# Tag_Reader_r1.net
KiCad netlist of a schematic drawn in EAGLE
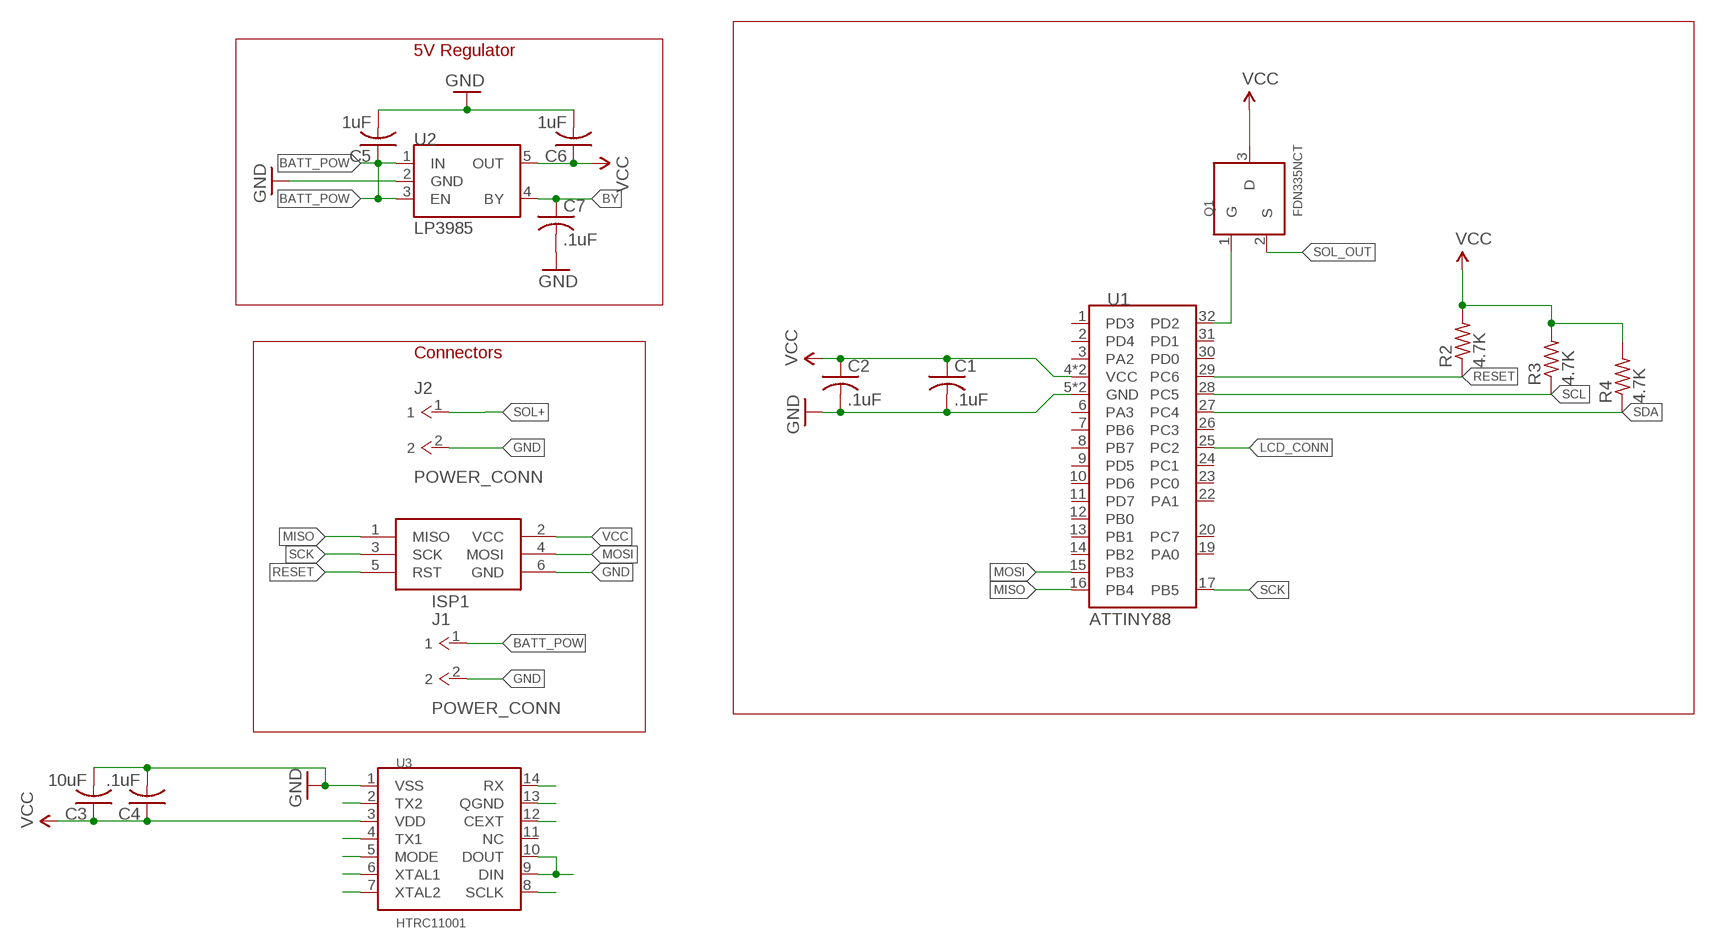
[diagram p0: schematic, sheet 1]

(export (version "E")
  (design (tool "Eeschema 10.0.6"))
  (components
    (comp (ref "C1")
      (value ".1uF")
      (footprint "eagle-import:C0603")
      (libsource (lib "eagle-import") (part "C-USC0603"))
    )
    (comp (ref "C2")
      (value ".1uF")
      (footprint "eagle-import:C0603")
      (libsource (lib "eagle-import") (part "C-USC0603"))
    )
    (comp (ref "C3")
      (value "10uF")
      (footprint "eagle-import:C0603")
      (libsource (lib "eagle-import") (part "C-USC0603"))
    )
    (comp (ref "C4")
      (value ".1uF")
      (footprint "eagle-import:C0603")
      (libsource (lib "eagle-import") (part "C-USC0603"))
    )
    (comp (ref "C5")
      (value "1uF")
      (footprint "eagle-import:C0603")
      (libsource (lib "eagle-import") (part "C-USC0603"))
    )
    (comp (ref "C6")
      (value "1uF")
      (footprint "eagle-import:C0603")
      (libsource (lib "eagle-import") (part "C-USC0603"))
    )
    (comp (ref "C7")
      (value ".1uF")
      (footprint "eagle-import:C0603")
      (libsource (lib "eagle-import") (part "C-USC0603"))
    )
    (comp (ref "ISP1")
      (value "AVRISP-6")
      (footprint "eagle-import:AVRISP")
      (libsource (lib "eagle-import") (part "AVRISP-6"))
    )
    (comp (ref "J1")
      (value "POWER_CONN")
      (footprint "eagle-import:640455_CONN")
      (libsource (lib "eagle-import") (part "POWER_CONN"))
    )
    (comp (ref "J2")
      (value "POWER_CONN")
      (footprint "eagle-import:640455_CONN")
      (libsource (lib "eagle-import") (part "POWER_CONN"))
    )
    (comp (ref "Q1")
      (value "FDN335NCT")
      (footprint "eagle-import:SOT23-3")
      (libsource (lib "eagle-import") (part "FDN335NCT"))
    )
    (comp (ref "R2")
      (value "4.7K")
      (footprint "eagle-import:R0603")
      (libsource (lib "eagle-import") (part "R-US_R0603"))
    )
    (comp (ref "R3")
      (value "4.7K")
      (footprint "eagle-import:R0603")
      (libsource (lib "eagle-import") (part "R-US_R0603"))
    )
    (comp (ref "R4")
      (value "4.7K")
      (footprint "eagle-import:R0603")
      (libsource (lib "eagle-import") (part "R-US_R0603"))
    )
    (comp (ref "U1")
      (value "ATTINY88")
      (footprint "eagle-import:32-TQFP")
      (libsource (lib "eagle-import") (part "ATTINY88"))
    )
    (comp (ref "U2")
      (value "LP3985")
      (footprint "eagle-import:SOT23-5")
      (libsource (lib "eagle-import") (part "LP3985"))
    )
    (comp (ref "U3")
      (value "HTRC11001")
      (footprint "eagle-import:14-SOIC")
      (libsource (lib "eagle-import") (part "HTRC11001"))
    )
  )
  (nets
    (net (code "1") (name "BATT_POW") (class "Default")
      (node (ref "C5") (pin "1") (pinfunction "1_1") (pintype "passive"))
      (node (ref "J1") (pin "1") (pinfunction "1_1") (pintype "bidirectional"))
      (node (ref "U2") (pin "1") (pinfunction "IN_1") (pintype "bidirectional"))
      (node (ref "U2") (pin "3") (pinfunction "EN_3") (pintype "bidirectional"))
    )
    (net (code "2") (name "BY") (class "Default")
      (node (ref "C7") (pin "1") (pinfunction "1_1") (pintype "passive"))
      (node (ref "U2") (pin "4") (pinfunction "BY_4") (pintype "bidirectional"))
    )
    (net (code "3") (name "GND") (class "Default")
      (node (ref "C1") (pin "2") (pinfunction "2_2") (pintype "passive"))
      (node (ref "C2") (pin "2") (pinfunction "2_2") (pintype "passive"))
      (node (ref "C3") (pin "2") (pinfunction "2_2") (pintype "passive"))
      (node (ref "C4") (pin "2") (pinfunction "2_2") (pintype "passive"))
      (node (ref "C5") (pin "2") (pinfunction "2_2") (pintype "passive"))
      (node (ref "C6") (pin "2") (pinfunction "2_2") (pintype "passive"))
      (node (ref "C7") (pin "2") (pinfunction "2_2") (pintype "passive"))
      (node (ref "ISP1") (pin "6") (pinfunction "GND_6") (pintype "power_in"))
      (node (ref "J1") (pin "2") (pinfunction "2_2") (pintype "bidirectional"))
      (node (ref "J2") (pin "2") (pinfunction "2_2") (pintype "bidirectional"))
      (node (ref "U1") (pin "21") (pinfunction "GND_21") (pintype "bidirectional"))
      (node (ref "U1") (pin "5") (pinfunction "GND_5") (pintype "bidirectional"))
      (node (ref "U2") (pin "2") (pinfunction "GND_2") (pintype "bidirectional"))
      (node (ref "U3") (pin "1") (pinfunction "VSS_1") (pintype "bidirectional"))
    )
    (net (code "4") (name "LCD_CONN") (class "Default")
      (node (ref "U1") (pin "25") (pinfunction "PC2_25") (pintype "bidirectional"))
    )
    (net (code "5") (name "MISO") (class "Default")
      (node (ref "ISP1") (pin "1") (pinfunction "MISO_1") (pintype "input"))
      (node (ref "U1") (pin "16") (pinfunction "PB4_16") (pintype "bidirectional"))
    )
    (net (code "6") (name "MOSI") (class "Default")
      (node (ref "ISP1") (pin "4") (pinfunction "MOSI_4") (pintype "output"))
      (node (ref "U1") (pin "15") (pinfunction "PB3_15") (pintype "bidirectional"))
    )
    (net (code "7") (name "Net-(Q1-G)") (class "Default")
      (node (ref "Q1") (pin "1") (pinfunction "G_1") (pintype "bidirectional"))
      (node (ref "U1") (pin "32") (pinfunction "PD2_32") (pintype "bidirectional"))
    )
    (net (code "8") (name "Net-(U3-DIN)") (class "Default")
      (node (ref "U3") (pin "10") (pinfunction "DOUT_10") (pintype "bidirectional"))
      (node (ref "U3") (pin "9") (pinfunction "DIN_9") (pintype "bidirectional"))
    )
    (net (code "9") (name "RESET") (class "Default")
      (node (ref "ISP1") (pin "5") (pinfunction "RST_5") (pintype "output"))
      (node (ref "R2") (pin "1") (pinfunction "1_1") (pintype "passive"))
      (node (ref "U1") (pin "29") (pinfunction "PC6_29") (pintype "bidirectional"))
    )
    (net (code "10") (name "SCK") (class "Default")
      (node (ref "ISP1") (pin "3") (pinfunction "SCK_3") (pintype "output"))
      (node (ref "U1") (pin "17") (pinfunction "PB5_17") (pintype "bidirectional"))
    )
    (net (code "11") (name "SCL") (class "Default")
      (node (ref "R3") (pin "1") (pinfunction "1_1") (pintype "passive"))
      (node (ref "U1") (pin "28") (pinfunction "PC5_28") (pintype "bidirectional"))
    )
    (net (code "12") (name "SDA") (class "Default")
      (node (ref "R4") (pin "1") (pinfunction "1_1") (pintype "passive"))
      (node (ref "U1") (pin "27") (pinfunction "PC4_27") (pintype "bidirectional"))
    )
    (net (code "13") (name "SOL+") (class "Default")
      (node (ref "J2") (pin "1") (pinfunction "1_1") (pintype "bidirectional"))
    )
    (net (code "14") (name "SOL_OUT") (class "Default")
      (node (ref "Q1") (pin "2") (pinfunction "S_2") (pintype "bidirectional"))
    )
    (net (code "15") (name "VCC") (class "Default")
      (node (ref "C1") (pin "1") (pinfunction "1_1") (pintype "passive"))
      (node (ref "C2") (pin "1") (pinfunction "1_1") (pintype "passive"))
      (node (ref "C3") (pin "1") (pinfunction "1_1") (pintype "passive"))
      (node (ref "C4") (pin "1") (pinfunction "1_1") (pintype "passive"))
      (node (ref "C6") (pin "1") (pinfunction "1_1") (pintype "passive"))
      (node (ref "ISP1") (pin "2") (pinfunction "VCC_2") (pintype "power_in"))
      (node (ref "Q1") (pin "3") (pinfunction "D_3") (pintype "bidirectional"))
      (node (ref "R2") (pin "2") (pinfunction "2_2") (pintype "passive"))
      (node (ref "R3") (pin "2") (pinfunction "2_2") (pintype "passive"))
      (node (ref "R4") (pin "2") (pinfunction "2_2") (pintype "passive"))
      (node (ref "U1") (pin "18") (pinfunction "VCC_18") (pintype "bidirectional"))
      (node (ref "U1") (pin "4") (pinfunction "VCC_4") (pintype "bidirectional"))
      (node (ref "U2") (pin "5") (pinfunction "OUT_5") (pintype "bidirectional"))
      (node (ref "U3") (pin "3") (pinfunction "VDD_3") (pintype "bidirectional"))
    )
    (net (code "16") (name "unconnected-(U1-PA0-Pad19)") (class "Default")
      (node (ref "U1") (pin "19") (pinfunction "PA0_19") (pintype "bidirectional"))
    )
    (net (code "17") (name "unconnected-(U1-PA1-Pad22)") (class "Default")
      (node (ref "U1") (pin "22") (pinfunction "PA1_22") (pintype "bidirectional"))
    )
    (net (code "18") (name "unconnected-(U1-PA2-Pad3)") (class "Default")
      (node (ref "U1") (pin "3") (pinfunction "PA2_3") (pintype "bidirectional"))
    )
    (net (code "19") (name "unconnected-(U1-PA3-Pad6)") (class "Default")
      (node (ref "U1") (pin "6") (pinfunction "PA3_6") (pintype "bidirectional"))
    )
    (net (code "20") (name "unconnected-(U1-PB0-Pad12)") (class "Default")
      (node (ref "U1") (pin "12") (pinfunction "PB0_12") (pintype "bidirectional"))
    )
    (net (code "21") (name "unconnected-(U1-PB1-Pad13)") (class "Default")
      (node (ref "U1") (pin "13") (pinfunction "PB1_13") (pintype "bidirectional"))
    )
    (net (code "22") (name "unconnected-(U1-PB2-Pad14)") (class "Default")
      (node (ref "U1") (pin "14") (pinfunction "PB2_14") (pintype "bidirectional"))
    )
    (net (code "23") (name "unconnected-(U1-PB6-Pad7)") (class "Default")
      (node (ref "U1") (pin "7") (pinfunction "PB6_7") (pintype "bidirectional"))
    )
    (net (code "24") (name "unconnected-(U1-PB7-Pad8)") (class "Default")
      (node (ref "U1") (pin "8") (pinfunction "PB7_8") (pintype "bidirectional"))
    )
    (net (code "25") (name "unconnected-(U1-PC0-Pad23)") (class "Default")
      (node (ref "U1") (pin "23") (pinfunction "PC0_23") (pintype "bidirectional"))
    )
    (net (code "26") (name "unconnected-(U1-PC1-Pad24)") (class "Default")
      (node (ref "U1") (pin "24") (pinfunction "PC1_24") (pintype "bidirectional"))
    )
    (net (code "27") (name "unconnected-(U1-PC3-Pad26)") (class "Default")
      (node (ref "U1") (pin "26") (pinfunction "PC3_26") (pintype "bidirectional"))
    )
    (net (code "28") (name "unconnected-(U1-PC7-Pad20)") (class "Default")
      (node (ref "U1") (pin "20") (pinfunction "PC7_20") (pintype "bidirectional"))
    )
    (net (code "29") (name "unconnected-(U1-PD0-Pad30)") (class "Default")
      (node (ref "U1") (pin "30") (pinfunction "PD0_30") (pintype "bidirectional"))
    )
    (net (code "30") (name "unconnected-(U1-PD1-Pad31)") (class "Default")
      (node (ref "U1") (pin "31") (pinfunction "PD1_31") (pintype "bidirectional"))
    )
    (net (code "31") (name "unconnected-(U1-PD3-Pad1)") (class "Default")
      (node (ref "U1") (pin "1") (pinfunction "PD3_1") (pintype "bidirectional"))
    )
    (net (code "32") (name "unconnected-(U1-PD4-Pad2)") (class "Default")
      (node (ref "U1") (pin "2") (pinfunction "PD4_2") (pintype "bidirectional"))
    )
    (net (code "33") (name "unconnected-(U1-PD5-Pad9)") (class "Default")
      (node (ref "U1") (pin "9") (pinfunction "PD5_9") (pintype "bidirectional"))
    )
    (net (code "34") (name "unconnected-(U1-PD6-Pad10)") (class "Default")
      (node (ref "U1") (pin "10") (pinfunction "PD6_10") (pintype "bidirectional"))
    )
    (net (code "35") (name "unconnected-(U1-PD7-Pad11)") (class "Default")
      (node (ref "U1") (pin "11") (pinfunction "PD7_11") (pintype "bidirectional"))
    )
    (net (code "36") (name "unconnected-(U3-CEXT-Pad12)") (class "Default")
      (node (ref "U3") (pin "12") (pinfunction "CEXT_12") (pintype "bidirectional"))
    )
    (net (code "37") (name "unconnected-(U3-MODE-Pad5)") (class "Default")
      (node (ref "U3") (pin "5") (pinfunction "MODE_5") (pintype "bidirectional"))
    )
    (net (code "38") (name "unconnected-(U3-NC-Pad11)") (class "Default")
      (node (ref "U3") (pin "11") (pinfunction "NC_11") (pintype "bidirectional"))
    )
    (net (code "39") (name "unconnected-(U3-QGND-Pad13)") (class "Default")
      (node (ref "U3") (pin "13") (pinfunction "QGND_13") (pintype "bidirectional"))
    )
    (net (code "40") (name "unconnected-(U3-RX-Pad14)") (class "Default")
      (node (ref "U3") (pin "14") (pinfunction "RX_14") (pintype "bidirectional"))
    )
    (net (code "41") (name "unconnected-(U3-SCLK-Pad8)") (class "Default")
      (node (ref "U3") (pin "8") (pinfunction "SCLK_8") (pintype "bidirectional"))
    )
    (net (code "42") (name "unconnected-(U3-TX1-Pad4)") (class "Default")
      (node (ref "U3") (pin "4") (pinfunction "TX1_4") (pintype "bidirectional"))
    )
    (net (code "43") (name "unconnected-(U3-TX2-Pad2)") (class "Default")
      (node (ref "U3") (pin "2") (pinfunction "TX2_2") (pintype "bidirectional"))
    )
    (net (code "44") (name "unconnected-(U3-XTAL1-Pad6)") (class "Default")
      (node (ref "U3") (pin "6") (pinfunction "XTAL1_6") (pintype "bidirectional"))
    )
    (net (code "45") (name "unconnected-(U3-XTAL2-Pad7)") (class "Default")
      (node (ref "U3") (pin "7") (pinfunction "XTAL2_7") (pintype "bidirectional"))
    )
  )
)
